# tritiled22_cr2477.net
KiCad netlist of a schematic drawn in EAGLE
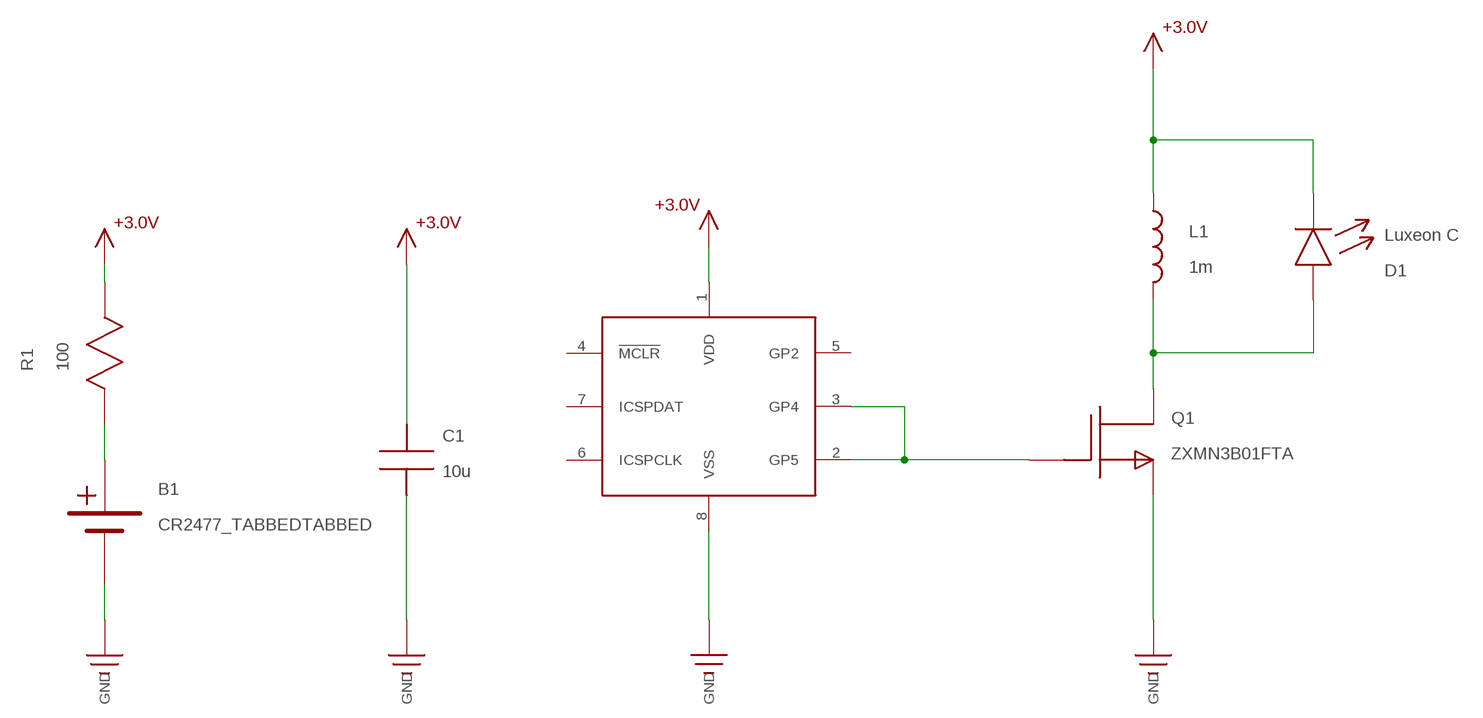
[diagram p0: schematic, sheet 1]

(export (version "E")
  (design (tool "Eeschema 10.0.6"))
  (components
    (comp (ref "B1")
      (value "CR2477_TABBEDTABBED")
      (footprint "eagle-import:CR2477_TABBED")
      (libsource (lib "eagle-import") (part "CR2477_TABBEDTABBED"))
    )
    (comp (ref "C1")
      (value "10u")
      (footprint "eagle-import:1206")
      (libsource (lib "eagle-import") (part "C1206"))
    )
    (comp (ref "D1")
      (value "Luxeon C")
      (footprint "eagle-import:LUXEON_C")
      (libsource (lib "eagle-import") (part "LEDLUXEON_C"))
    )
    (comp (ref "L1")
      (value "1m")
      (footprint "eagle-import:SRR6028_INDUCTOR")
      (libsource (lib "eagle-import") (part "SRR6028_INDUCTOR"))
    )
    (comp (ref "Q1")
      (value "ZXMN3B01FTA")
      (footprint "eagle-import:SOT-23")
      (libsource (lib "eagle-import") (part "ZXMN3B01FSOT23"))
    )
    (comp (ref "R1")
      (value "100")
      (footprint "eagle-import:R1206")
      (libsource (lib "eagle-import") (part "R1206"))
    )
    (comp (ref "U1")
      (value "PIC12LF1571")
      (footprint "eagle-import:SOIC8")
      (libsource (lib "eagle-import") (part "PIC12LF1571"))
    )
  )
  (nets
    (net (code "1") (name "+3.0V") (class "Default")
      (node (ref "C1") (pin "P$1") (pinfunction "P$1_P$1") (pintype "bidirectional"))
      (node (ref "D1") (pin "C") (pinfunction "C_C") (pintype "bidirectional"))
      (node (ref "L1") (pin "P$1") (pinfunction "1_P$1") (pintype "passive"))
      (node (ref "R1") (pin "P$2") (pinfunction "P$2_P$2") (pintype "bidirectional"))
      (node (ref "U1") (pin "1") (pinfunction "VDD_1") (pintype "bidirectional"))
    )
    (net (code "2") (name "GND") (class "Default")
      (node (ref "B1") (pin "GND") (pinfunction "0V_GND") (pintype "power_in"))
      (node (ref "C1") (pin "P$2") (pinfunction "P$2_P$2") (pintype "bidirectional"))
      (node (ref "Q1") (pin "2") (pinfunction "S_2") (pintype "bidirectional"))
      (node (ref "U1") (pin "8") (pinfunction "VSS_8") (pintype "bidirectional"))
    )
    (net (code "3") (name "Net-(B1-+V)") (class "Default")
      (node (ref "B1") (pin "+3V") (pinfunction "+V_+3V") (pintype "power_in"))
      (node (ref "R1") (pin "P$1") (pinfunction "P$1_P$1") (pintype "bidirectional"))
    )
    (net (code "4") (name "Net-(L1-2)") (class "Default")
      (node (ref "D1") (pin "A") (pinfunction "A_A") (pintype "bidirectional"))
      (node (ref "L1") (pin "P$2") (pinfunction "2_P$2") (pintype "passive"))
      (node (ref "Q1") (pin "3") (pinfunction "D_3") (pintype "bidirectional"))
    )
    (net (code "5") (name "Net-(Q1-G)") (class "Default")
      (node (ref "Q1") (pin "1") (pinfunction "G_1") (pintype "bidirectional"))
      (node (ref "U1") (pin "2") (pinfunction "GP5_2") (pintype "bidirectional"))
      (node (ref "U1") (pin "3") (pinfunction "GP4_3") (pintype "bidirectional"))
    )
    (net (code "6") (name "unconnected-(U1-GP2-Pad5)") (class "Default")
      (node (ref "U1") (pin "5") (pinfunction "GP2_5") (pintype "bidirectional"))
    )
    (net (code "7") (name "unconnected-(U1-ICSPCLK-Pad6)") (class "Default")
      (node (ref "U1") (pin "6") (pinfunction "ICSPCLK_6") (pintype "bidirectional"))
    )
    (net (code "8") (name "unconnected-(U1-ICSPDAT-Pad7)") (class "Default")
      (node (ref "U1") (pin "7") (pinfunction "ICSPDAT_7") (pintype "bidirectional"))
    )
    (net (code "9") (name "unconnected-(U1-~{MCLR}-Pad4)") (class "Default")
      (node (ref "U1") (pin "4") (pinfunction "~{MCLR}_4") (pintype "bidirectional"))
    )
  )
)
